# 2656.net
KiCad netlist of a schematic drawn in EAGLE
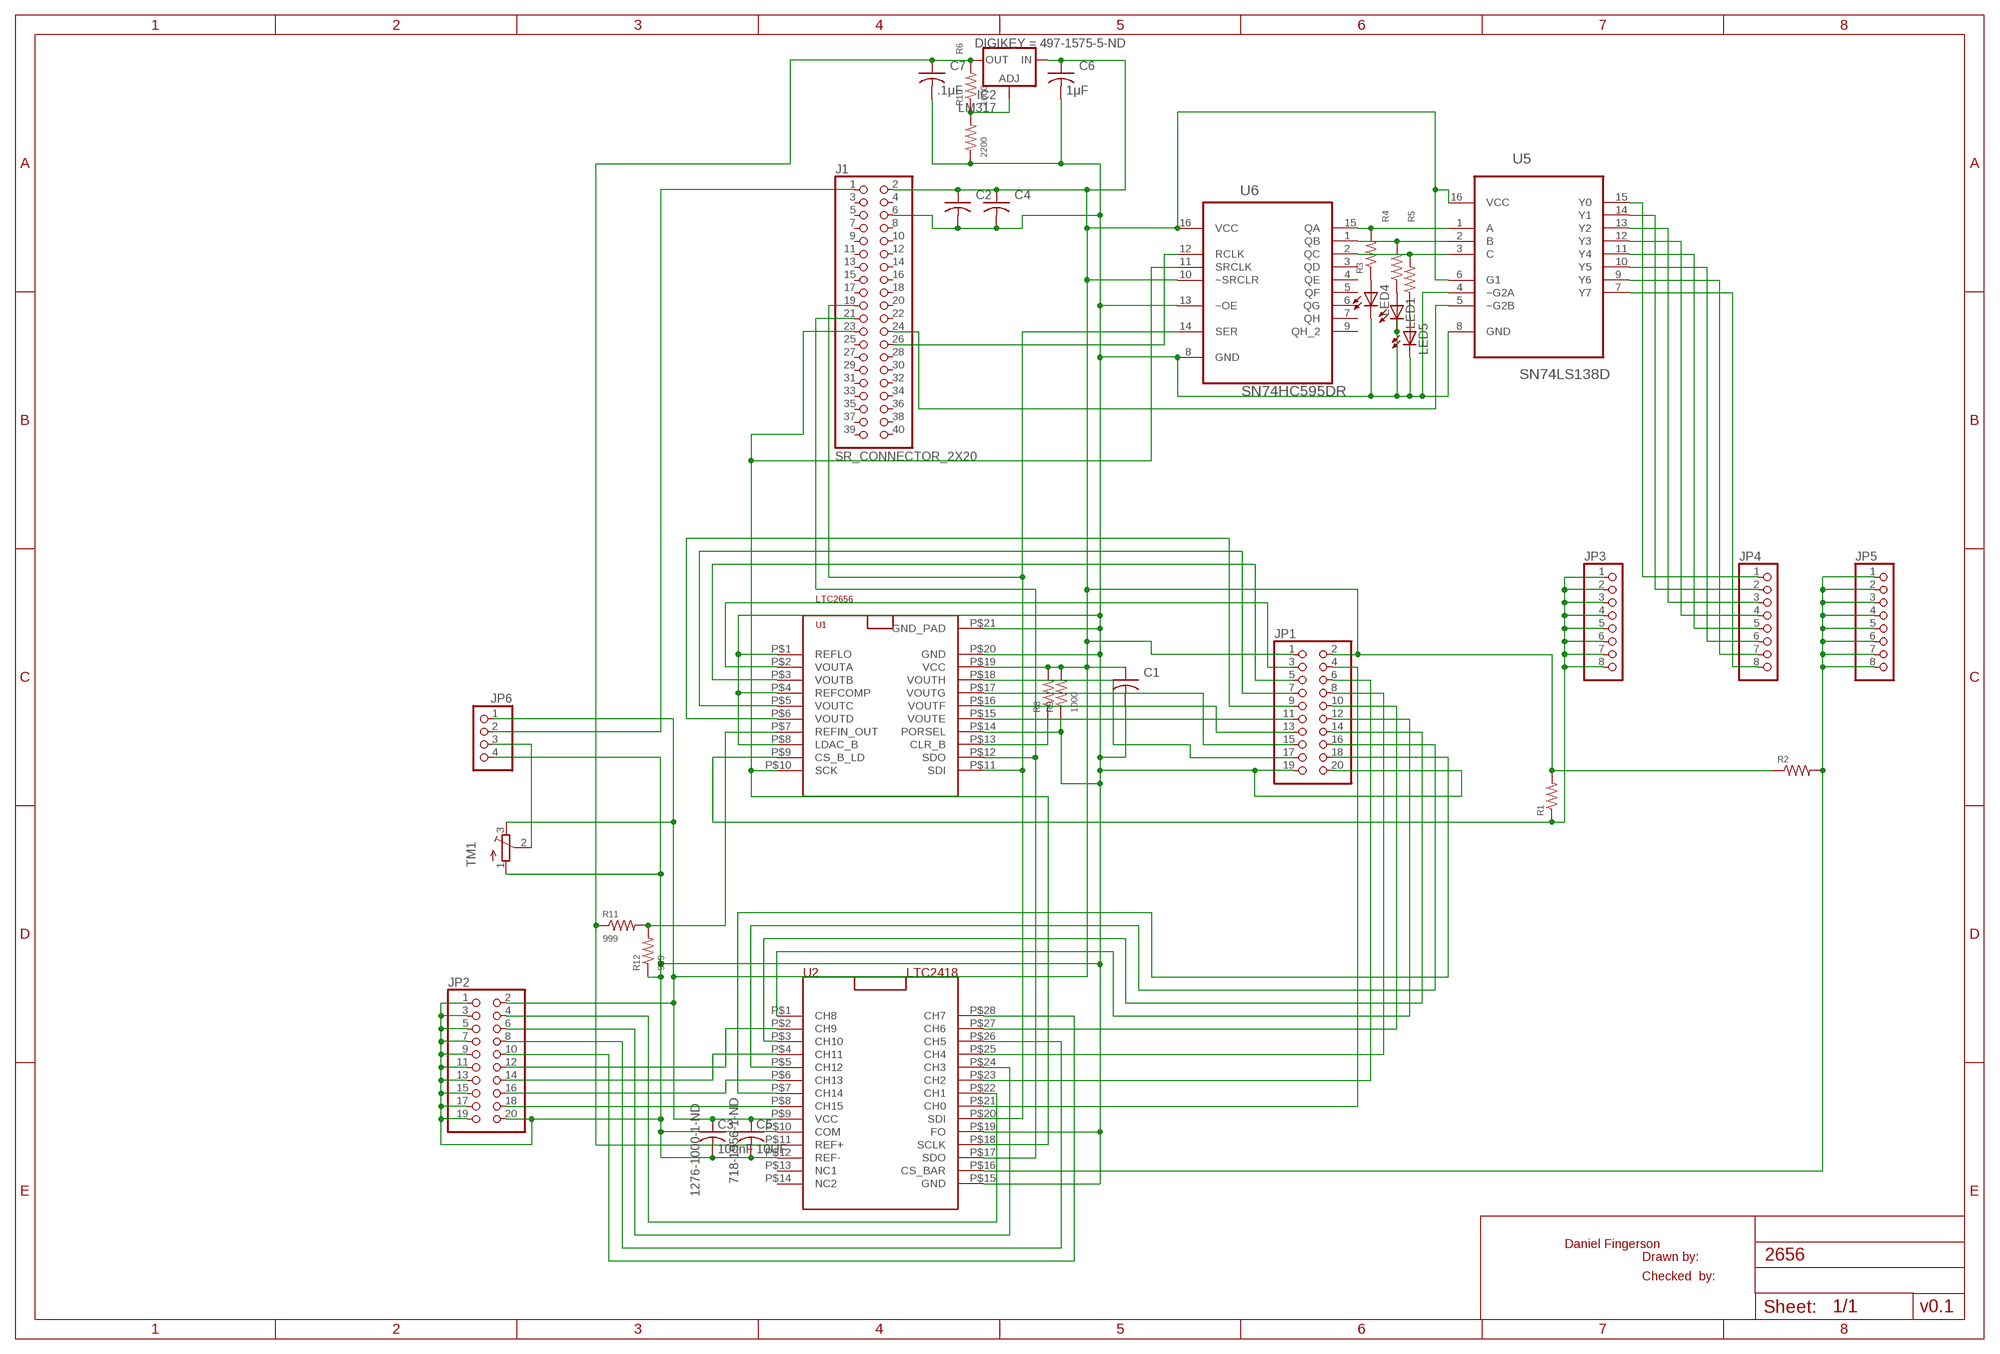
[diagram p0: schematic, sheet 1]

(export (version "E")
  (design (tool "Eeschema 10.0.6"))
  (components
    (comp (ref "C1")
      (value "C-USC1206")
      (footprint "eagle-import:C1206")
      (libsource (lib "eagle-import") (part "C-USC1206"))
    )
    (comp (ref "C2")
      (value "C-USC1206")
      (footprint "eagle-import:C1206")
      (libsource (lib "eagle-import") (part "C-USC1206"))
    )
    (comp (ref "C3")
      (value "100nF")
      (footprint "eagle-import:C1206")
      (fields (field (name "DIGIKEY") "1276-1000-1-ND"))
      (libsource (lib "eagle-import") (part "C-USC1206"))
    )
    (comp (ref "C4")
      (value "C-USC1206")
      (footprint "eagle-import:C1206")
      (libsource (lib "eagle-import") (part "C-USC1206"))
    )
    (comp (ref "C5")
      (value "10UF")
      (footprint "eagle-import:C1206")
      (fields (field (name "DIGIKEY") "718-1956-1-ND"))
      (libsource (lib "eagle-import") (part "C-USC1206"))
    )
    (comp (ref "C6")
      (value "1μF")
      (footprint "eagle-import:C1206")
      (libsource (lib "eagle-import") (part "C-USC1206"))
    )
    (comp (ref "C7")
      (value ".1μF")
      (footprint "eagle-import:C1206")
      (libsource (lib "eagle-import") (part "C-USC1206"))
    )
    (comp (ref "IC2")
      (value "LM317")
      (footprint "eagle-import:317TL")
      (fields (field (name "DIGIKEY") "497-1575-5-ND"))
      (libsource (lib "eagle-import") (part "LM317TL"))
    )
    (comp (ref "J1")
      (value "SR_CONNECTOR_2X20")
      (footprint "eagle-import:SR_CONNECTOR_2X20")
      (libsource (lib "eagle-import") (part "SR_CONNECTOR_2X20"))
    )
    (comp (ref "JP1")
      (value "PINHD-2X10")
      (footprint "eagle-import:2X10")
      (libsource (lib "eagle-import") (part "PINHD-2X10"))
    )
    (comp (ref "JP2")
      (value "PINHD-2X10")
      (footprint "eagle-import:2X10")
      (libsource (lib "eagle-import") (part "PINHD-2X10"))
    )
    (comp (ref "JP3")
      (value "PINHD-1X8BIG")
      (footprint "eagle-import:1X08-BIG")
      (libsource (lib "eagle-import") (part "PINHD-1X8BIG"))
    )
    (comp (ref "JP4")
      (value "PINHD-1X8BIG")
      (footprint "eagle-import:1X08-BIG")
      (libsource (lib "eagle-import") (part "PINHD-1X8BIG"))
    )
    (comp (ref "JP5")
      (value "PINHD-1X8BIG")
      (footprint "eagle-import:1X08-BIG")
      (libsource (lib "eagle-import") (part "PINHD-1X8BIG"))
    )
    (comp (ref "JP6")
      (value "PINHD-1X4")
      (footprint "eagle-import:1X04")
      (libsource (lib "eagle-import") (part "PINHD-1X4"))
    )
    (comp (ref "LED1")
      (value "LEDCHIPLED_1206")
      (footprint "eagle-import:CHIPLED_1206")
      (libsource (lib "eagle-import") (part "LEDCHIPLED_1206"))
    )
    (comp (ref "LED4")
      (value "LEDCHIPLED_1206")
      (footprint "eagle-import:CHIPLED_1206")
      (libsource (lib "eagle-import") (part "LEDCHIPLED_1206"))
    )
    (comp (ref "LED5")
      (value "LEDCHIPLED_1206")
      (footprint "eagle-import:CHIPLED_1206")
      (libsource (lib "eagle-import") (part "LEDCHIPLED_1206"))
    )
    (comp (ref "R1")
      (value "R-US_R1206")
      (footprint "eagle-import:R1206")
      (libsource (lib "eagle-import") (part "R-US_R1206"))
    )
    (comp (ref "R2")
      (value "R-US_R1206")
      (footprint "eagle-import:R1206")
      (libsource (lib "eagle-import") (part "R-US_R1206"))
    )
    (comp (ref "R3")
      (value "R-US_R1206")
      (footprint "eagle-import:R1206")
      (libsource (lib "eagle-import") (part "R-US_R1206"))
    )
    (comp (ref "R4")
      (value "R-US_R1206")
      (footprint "eagle-import:R1206")
      (libsource (lib "eagle-import") (part "R-US_R1206"))
    )
    (comp (ref "R5")
      (value "R-US_R1206")
      (footprint "eagle-import:R1206")
      (libsource (lib "eagle-import") (part "R-US_R1206"))
    )
    (comp (ref "R6")
      (value "1000")
      (footprint "eagle-import:R1206")
      (libsource (lib "eagle-import") (part "R-US_R1206"))
    )
    (comp (ref "R8")
      (value "R-US_R1206")
      (footprint "eagle-import:R1206")
      (libsource (lib "eagle-import") (part "R-US_R1206"))
    )
    (comp (ref "R9")
      (value "1000")
      (footprint "eagle-import:R1206")
      (libsource (lib "eagle-import") (part "R-US_R1206"))
    )
    (comp (ref "R10")
      (value "2200")
      (footprint "eagle-import:R1206")
      (libsource (lib "eagle-import") (part "R-US_R1206"))
    )
    (comp (ref "R11")
      (value "999")
      (footprint "eagle-import:R1206")
      (libsource (lib "eagle-import") (part "R-US_R1206"))
    )
    (comp (ref "R12")
      (value "999")
      (footprint "eagle-import:R1206")
      (libsource (lib "eagle-import") (part "R-US_R1206"))
    )
    (comp (ref "TM1")
      (value "TRIMPOT3386")
      (footprint "eagle-import:TRIM-3386")
      (libsource (lib "eagle-import") (part "TRIMPOT3386"))
    )
    (comp (ref "U1")
      (value "LTC2656")
      (footprint "eagle-import:SR_TSSOP20")
      (libsource (lib "eagle-import") (part "LTC2656"))
    )
    (comp (ref "U2")
      (value "LTC2418")
      (footprint "eagle-import:SR_SSOP28")
      (libsource (lib "eagle-import") (part "LTC2418"))
    )
    (comp (ref "U5")
      (value "SN74LS138D")
      (footprint "eagle-import:SOIC127P600X175-16N")
      (libsource (lib "eagle-import") (part "SN74LS138D"))
    )
    (comp (ref "U6")
      (value "SN74HC595DR")
      (footprint "eagle-import:SOIC127P600X175-16N")
      (fields (field (name "SPICEPREFIX") "X"))
      (libsource (lib "eagle-import") (part "SN74HC595DR"))
    )
  )
  (nets
    (net (code "1") (name "Net-(IC2-ADJ)") (class "Default")
      (node (ref "IC2") (pin "1") (pinfunction "ADJ_1") (pintype "input"))
      (node (ref "R10") (pin "2") (pinfunction "2_2") (pintype "passive"))
      (node (ref "R6") (pin "1") (pinfunction "1_1") (pintype "passive"))
    )
    (net (code "2") (name "Net-(IC2-IN)") (class "Default")
      (node (ref "C1") (pin "1") (pinfunction "1_1") (pintype "passive"))
      (node (ref "C2") (pin "1") (pinfunction "1_1") (pintype "passive"))
      (node (ref "C3") (pin "1") (pinfunction "1_1") (pintype "passive"))
      (node (ref "C4") (pin "1") (pinfunction "1_1") (pintype "passive"))
      (node (ref "C5") (pin "1") (pinfunction "1_1") (pintype "passive"))
      (node (ref "C6") (pin "1") (pinfunction "1_1") (pintype "passive"))
      (node (ref "IC2") (pin "3") (pinfunction "IN_3") (pintype "input"))
      (node (ref "J1") (pin "2") (pinfunction "2_2") (pintype "passive"))
      (node (ref "JP1") (pin "1") (pinfunction "1_1") (pintype "passive"))
      (node (ref "JP1") (pin "2") (pinfunction "2_2") (pintype "passive"))
      (node (ref "JP2") (pin "2") (pinfunction "2_2") (pintype "passive"))
      (node (ref "JP6") (pin "1") (pinfunction "1_1") (pintype "passive"))
      (node (ref "R1") (pin "2") (pinfunction "2_2") (pintype "passive"))
      (node (ref "R2") (pin "1") (pinfunction "1_1") (pintype "passive"))
      (node (ref "R8") (pin "2") (pinfunction "2_2") (pintype "passive"))
      (node (ref "R9") (pin "2") (pinfunction "2_2") (pintype "passive"))
      (node (ref "TM1") (pin "3") (pinfunction "E_3") (pintype "passive"))
      (node (ref "U1") (pin "P$19") (pinfunction "VCC_P$19") (pintype "bidirectional"))
      (node (ref "U2") (pin "P$9") (pinfunction "VCC_P$9") (pintype "bidirectional"))
      (node (ref "U5") (pin "16") (pinfunction "VCC_16") (pintype "power_in"))
      (node (ref "U5") (pin "6") (pinfunction "G1_6") (pintype "input"))
      (node (ref "U6") (pin "10") (pinfunction "~{SRCLR}_10") (pintype "input"))
      (node (ref "U6") (pin "16") (pinfunction "VCC_16") (pintype "power_in"))
    )
    (net (code "3") (name "Net-(IC2-OUT)") (class "Default")
      (node (ref "C7") (pin "1") (pinfunction "1_1") (pintype "passive"))
      (node (ref "IC2") (pin "2") (pinfunction "OUT_2") (pintype "passive"))
      (node (ref "R11") (pin "1") (pinfunction "1_1") (pintype "passive"))
      (node (ref "R6") (pin "2") (pinfunction "2_2") (pintype "passive"))
      (node (ref "U2") (pin "P$11") (pinfunction "REF+_P$11") (pintype "bidirectional"))
    )
    (net (code "4") (name "Net-(J1-Pad1)") (class "Default")
      (node (ref "J1") (pin "1") (pinfunction "1_1") (pintype "passive"))
      (node (ref "JP6") (pin "2") (pinfunction "2_2") (pintype "passive"))
    )
    (net (code "5") (name "Net-(LED1-PadA)") (class "Default")
      (node (ref "LED1") (pin "A") (pinfunction "A_A") (pintype "passive"))
      (node (ref "R4") (pin "1") (pinfunction "1_1") (pintype "passive"))
    )
    (net (code "6") (name "Net-(LED4-PadA)") (class "Default")
      (node (ref "LED4") (pin "A") (pinfunction "A_A") (pintype "passive"))
      (node (ref "R3") (pin "1") (pinfunction "1_1") (pintype "passive"))
    )
    (net (code "7") (name "Net-(LED5-PadA)") (class "Default")
      (node (ref "LED5") (pin "A") (pinfunction "A_A") (pintype "passive"))
      (node (ref "R5") (pin "1") (pinfunction "1_1") (pintype "passive"))
    )
    (net (code "8") (name "Net-(TM1-A)") (class "Default")
      (node (ref "C1") (pin "2") (pinfunction "2_2") (pintype "passive"))
      (node (ref "C2") (pin "2") (pinfunction "2_2") (pintype "passive"))
      (node (ref "C3") (pin "2") (pinfunction "2_2") (pintype "passive"))
      (node (ref "C4") (pin "2") (pinfunction "2_2") (pintype "passive"))
      (node (ref "C5") (pin "2") (pinfunction "2_2") (pintype "passive"))
      (node (ref "C6") (pin "2") (pinfunction "2_2") (pintype "passive"))
      (node (ref "C7") (pin "2") (pinfunction "2_2") (pintype "passive"))
      (node (ref "J1") (pin "6") (pinfunction "6_6") (pintype "passive"))
      (node (ref "JP1") (pin "19") (pinfunction "19_19") (pintype "passive"))
      (node (ref "JP1") (pin "20") (pinfunction "20_20") (pintype "passive"))
      (node (ref "JP2") (pin "1") (pinfunction "1_1") (pintype "passive"))
      (node (ref "JP2") (pin "11") (pinfunction "11_11") (pintype "passive"))
      (node (ref "JP2") (pin "13") (pinfunction "13_13") (pintype "passive"))
      (node (ref "JP2") (pin "15") (pinfunction "15_15") (pintype "passive"))
      (node (ref "JP2") (pin "17") (pinfunction "17_17") (pintype "passive"))
      (node (ref "JP2") (pin "19") (pinfunction "19_19") (pintype "passive"))
      (node (ref "JP2") (pin "20") (pinfunction "20_20") (pintype "passive"))
      (node (ref "JP2") (pin "3") (pinfunction "3_3") (pintype "passive"))
      (node (ref "JP2") (pin "5") (pinfunction "5_5") (pintype "passive"))
      (node (ref "JP2") (pin "7") (pinfunction "7_7") (pintype "passive"))
      (node (ref "JP2") (pin "9") (pinfunction "9_9") (pintype "passive"))
      (node (ref "JP6") (pin "4") (pinfunction "4_4") (pintype "passive"))
      (node (ref "LED1") (pin "C") (pinfunction "C_C") (pintype "passive"))
      (node (ref "LED4") (pin "C") (pinfunction "C_C") (pintype "passive"))
      (node (ref "LED5") (pin "C") (pinfunction "C_C") (pintype "passive"))
      (node (ref "R10") (pin "1") (pinfunction "1_1") (pintype "passive"))
      (node (ref "R12") (pin "1") (pinfunction "1_1") (pintype "passive"))
      (node (ref "R9") (pin "1") (pinfunction "1_1") (pintype "passive"))
      (node (ref "TM1") (pin "1") (pinfunction "A_1") (pintype "passive"))
      (node (ref "U1") (pin "P$1") (pinfunction "REFLO_P$1") (pintype "bidirectional"))
      (node (ref "U1") (pin "P$14") (pinfunction "PORSEL_P$14") (pintype "bidirectional"))
      (node (ref "U1") (pin "P$20") (pinfunction "GND_P$20") (pintype "bidirectional"))
      (node (ref "U1") (pin "P$21") (pinfunction "GND_PAD_P$21") (pintype "bidirectional"))
      (node (ref "U1") (pin "P$4") (pinfunction "REFCOMP_P$4") (pintype "bidirectional"))
      (node (ref "U1") (pin "P$8") (pinfunction "LDAC_B_P$8") (pintype "bidirectional"))
      (node (ref "U2") (pin "P$10") (pinfunction "COM_P$10") (pintype "bidirectional"))
      (node (ref "U2") (pin "P$12") (pinfunction "REF-_P$12") (pintype "bidirectional"))
      (node (ref "U2") (pin "P$15") (pinfunction "GND_P$15") (pintype "bidirectional"))
      (node (ref "U2") (pin "P$19") (pinfunction "FO_P$19") (pintype "bidirectional"))
      (node (ref "U5") (pin "4") (pinfunction "~{G2A}_4") (pintype "input"))
      (node (ref "U5") (pin "8") (pinfunction "GND_8") (pintype "passive"))
      (node (ref "U6") (pin "13") (pinfunction "~{OE}_13") (pintype "input"))
      (node (ref "U6") (pin "8") (pinfunction "GND_8") (pintype "passive"))
    )
    (net (code "9") (name "Net-(TM1-S)") (class "Default")
      (node (ref "JP6") (pin "3") (pinfunction "3_3") (pintype "passive"))
      (node (ref "TM1") (pin "2") (pinfunction "S_2") (pintype "passive"))
    )
    (net (code "10") (name "Net-(U1-CLR_B)") (class "Default")
      (node (ref "R8") (pin "1") (pinfunction "1_1") (pintype "passive"))
      (node (ref "U1") (pin "P$13") (pinfunction "CLR_B_P$13") (pintype "bidirectional"))
    )
    (net (code "11") (name "Net-(U1-CS_B_LD)") (class "Default")
      (node (ref "JP3") (pin "1") (pinfunction "1_1") (pintype "passive"))
      (node (ref "JP3") (pin "2") (pinfunction "2_2") (pintype "passive"))
      (node (ref "JP3") (pin "3") (pinfunction "3_3") (pintype "passive"))
      (node (ref "JP3") (pin "4") (pinfunction "4_4") (pintype "passive"))
      (node (ref "JP3") (pin "5") (pinfunction "5_5") (pintype "passive"))
      (node (ref "JP3") (pin "6") (pinfunction "6_6") (pintype "passive"))
      (node (ref "JP3") (pin "7") (pinfunction "7_7") (pintype "passive"))
      (node (ref "JP3") (pin "8") (pinfunction "8_8") (pintype "passive"))
      (node (ref "R1") (pin "1") (pinfunction "1_1") (pintype "passive"))
      (node (ref "U1") (pin "P$9") (pinfunction "CS_B_LD_P$9") (pintype "bidirectional"))
    )
    (net (code "12") (name "Net-(U1-REFIN_OUT)") (class "Default")
      (node (ref "R11") (pin "2") (pinfunction "2_2") (pintype "passive"))
      (node (ref "R12") (pin "2") (pinfunction "2_2") (pintype "passive"))
      (node (ref "U1") (pin "P$7") (pinfunction "REFIN_OUT_P$7") (pintype "bidirectional"))
    )
    (net (code "13") (name "Net-(U1-SCK)") (class "Default")
      (node (ref "J1") (pin "23") (pinfunction "23_23") (pintype "passive"))
      (node (ref "U1") (pin "P$10") (pinfunction "SCK_P$10") (pintype "bidirectional"))
      (node (ref "U2") (pin "P$18") (pinfunction "SCLK_P$18") (pintype "bidirectional"))
      (node (ref "U6") (pin "11") (pinfunction "SRCLK_11") (pintype "input"))
    )
    (net (code "14") (name "Net-(U1-SDI)") (class "Default")
      (node (ref "J1") (pin "19") (pinfunction "19_19") (pintype "passive"))
      (node (ref "U1") (pin "P$11") (pinfunction "SDI_P$11") (pintype "bidirectional"))
      (node (ref "U2") (pin "P$20") (pinfunction "SDI_P$20") (pintype "bidirectional"))
      (node (ref "U6") (pin "14") (pinfunction "SER_14") (pintype "input"))
    )
    (net (code "15") (name "Net-(U1-SDO)") (class "Default")
      (node (ref "J1") (pin "21") (pinfunction "21_21") (pintype "passive"))
      (node (ref "U1") (pin "P$12") (pinfunction "SDO_P$12") (pintype "bidirectional"))
      (node (ref "U2") (pin "P$17") (pinfunction "SDO_P$17") (pintype "bidirectional"))
    )
    (net (code "16") (name "Net-(U1-VOUTA)") (class "Default")
      (node (ref "JP1") (pin "3") (pinfunction "3_3") (pintype "passive"))
      (node (ref "U1") (pin "P$2") (pinfunction "VOUTA_P$2") (pintype "bidirectional"))
    )
    (net (code "17") (name "Net-(U1-VOUTB)") (class "Default")
      (node (ref "JP1") (pin "5") (pinfunction "5_5") (pintype "passive"))
      (node (ref "U1") (pin "P$3") (pinfunction "VOUTB_P$3") (pintype "bidirectional"))
    )
    (net (code "18") (name "Net-(U1-VOUTC)") (class "Default")
      (node (ref "JP1") (pin "7") (pinfunction "7_7") (pintype "passive"))
      (node (ref "U1") (pin "P$5") (pinfunction "VOUTC_P$5") (pintype "bidirectional"))
    )
    (net (code "19") (name "Net-(U1-VOUTD)") (class "Default")
      (node (ref "JP1") (pin "9") (pinfunction "9_9") (pintype "passive"))
      (node (ref "U1") (pin "P$6") (pinfunction "VOUTD_P$6") (pintype "bidirectional"))
    )
    (net (code "20") (name "Net-(U1-VOUTE)") (class "Default")
      (node (ref "JP1") (pin "11") (pinfunction "11_11") (pintype "passive"))
      (node (ref "U1") (pin "P$15") (pinfunction "VOUTE_P$15") (pintype "bidirectional"))
    )
    (net (code "21") (name "Net-(U1-VOUTF)") (class "Default")
      (node (ref "JP1") (pin "13") (pinfunction "13_13") (pintype "passive"))
      (node (ref "U1") (pin "P$16") (pinfunction "VOUTF_P$16") (pintype "bidirectional"))
    )
    (net (code "22") (name "Net-(U1-VOUTG)") (class "Default")
      (node (ref "JP1") (pin "15") (pinfunction "15_15") (pintype "passive"))
      (node (ref "U1") (pin "P$17") (pinfunction "VOUTG_P$17") (pintype "bidirectional"))
    )
    (net (code "23") (name "Net-(U1-VOUTH)") (class "Default")
      (node (ref "JP1") (pin "17") (pinfunction "17_17") (pintype "passive"))
      (node (ref "U1") (pin "P$18") (pinfunction "VOUTH_P$18") (pintype "bidirectional"))
    )
    (net (code "24") (name "Net-(U2-CH0)") (class "Default")
      (node (ref "JP1") (pin "4") (pinfunction "4_4") (pintype "passive"))
      (node (ref "U2") (pin "P$21") (pinfunction "CH0_P$21") (pintype "bidirectional"))
    )
    (net (code "25") (name "Net-(U2-CH1)") (class "Default")
      (node (ref "JP2") (pin "4") (pinfunction "4_4") (pintype "passive"))
      (node (ref "U2") (pin "P$22") (pinfunction "CH1_P$22") (pintype "bidirectional"))
    )
    (net (code "26") (name "Net-(U2-CH2)") (class "Default")
      (node (ref "JP1") (pin "6") (pinfunction "6_6") (pintype "passive"))
      (node (ref "U2") (pin "P$23") (pinfunction "CH2_P$23") (pintype "bidirectional"))
    )
    (net (code "27") (name "Net-(U2-CH3)") (class "Default")
      (node (ref "JP2") (pin "6") (pinfunction "6_6") (pintype "passive"))
      (node (ref "U2") (pin "P$24") (pinfunction "CH3_P$24") (pintype "bidirectional"))
    )
    (net (code "28") (name "Net-(U2-CH4)") (class "Default")
      (node (ref "JP1") (pin "8") (pinfunction "8_8") (pintype "passive"))
      (node (ref "U2") (pin "P$25") (pinfunction "CH4_P$25") (pintype "bidirectional"))
    )
    (net (code "29") (name "Net-(U2-CH5)") (class "Default")
      (node (ref "JP2") (pin "8") (pinfunction "8_8") (pintype "passive"))
      (node (ref "U2") (pin "P$26") (pinfunction "CH5_P$26") (pintype "bidirectional"))
    )
    (net (code "30") (name "Net-(U2-CH6)") (class "Default")
      (node (ref "JP1") (pin "10") (pinfunction "10_10") (pintype "passive"))
      (node (ref "U2") (pin "P$27") (pinfunction "CH6_P$27") (pintype "bidirectional"))
    )
    (net (code "31") (name "Net-(U2-CH7)") (class "Default")
      (node (ref "JP2") (pin "10") (pinfunction "10_10") (pintype "passive"))
      (node (ref "U2") (pin "P$28") (pinfunction "CH7_P$28") (pintype "bidirectional"))
    )
    (net (code "32") (name "Net-(U2-CH8)") (class "Default")
      (node (ref "JP1") (pin "12") (pinfunction "12_12") (pintype "passive"))
      (node (ref "U2") (pin "P$1") (pinfunction "CH8_P$1") (pintype "bidirectional"))
    )
    (net (code "33") (name "Net-(U2-CH9)") (class "Default")
      (node (ref "JP2") (pin "12") (pinfunction "12_12") (pintype "passive"))
      (node (ref "U2") (pin "P$2") (pinfunction "CH9_P$2") (pintype "bidirectional"))
    )
    (net (code "34") (name "Net-(U2-CH10)") (class "Default")
      (node (ref "JP1") (pin "14") (pinfunction "14_14") (pintype "passive"))
      (node (ref "U2") (pin "P$3") (pinfunction "CH10_P$3") (pintype "bidirectional"))
    )
    (net (code "35") (name "Net-(U2-CH11)") (class "Default")
      (node (ref "JP2") (pin "14") (pinfunction "14_14") (pintype "passive"))
      (node (ref "U2") (pin "P$4") (pinfunction "CH11_P$4") (pintype "bidirectional"))
    )
    (net (code "36") (name "Net-(U2-CH12)") (class "Default")
      (node (ref "JP1") (pin "16") (pinfunction "16_16") (pintype "passive"))
      (node (ref "U2") (pin "P$5") (pinfunction "CH12_P$5") (pintype "bidirectional"))
    )
    (net (code "37") (name "Net-(U2-CH13)") (class "Default")
      (node (ref "JP2") (pin "16") (pinfunction "16_16") (pintype "passive"))
      (node (ref "U2") (pin "P$6") (pinfunction "CH13_P$6") (pintype "bidirectional"))
    )
    (net (code "38") (name "Net-(U2-CH14)") (class "Default")
      (node (ref "JP1") (pin "18") (pinfunction "18_18") (pintype "passive"))
      (node (ref "U2") (pin "P$7") (pinfunction "CH14_P$7") (pintype "bidirectional"))
    )
    (net (code "39") (name "Net-(U2-CH15)") (class "Default")
      (node (ref "JP2") (pin "18") (pinfunction "18_18") (pintype "passive"))
      (node (ref "U2") (pin "P$8") (pinfunction "CH15_P$8") (pintype "bidirectional"))
    )
    (net (code "40") (name "Net-(U2-CS_BAR)") (class "Default")
      (node (ref "JP5") (pin "1") (pinfunction "1_1") (pintype "passive"))
      (node (ref "JP5") (pin "2") (pinfunction "2_2") (pintype "passive"))
      (node (ref "JP5") (pin "3") (pinfunction "3_3") (pintype "passive"))
      (node (ref "JP5") (pin "4") (pinfunction "4_4") (pintype "passive"))
      (node (ref "JP5") (pin "5") (pinfunction "5_5") (pintype "passive"))
      (node (ref "JP5") (pin "6") (pinfunction "6_6") (pintype "passive"))
      (node (ref "JP5") (pin "7") (pinfunction "7_7") (pintype "passive"))
      (node (ref "JP5") (pin "8") (pinfunction "8_8") (pintype "passive"))
      (node (ref "R2") (pin "2") (pinfunction "2_2") (pintype "passive"))
      (node (ref "U2") (pin "P$16") (pinfunction "CS_BAR_P$16") (pintype "bidirectional"))
    )
    (net (code "41") (name "Net-(U5-A)") (class "Default")
      (node (ref "R3") (pin "2") (pinfunction "2_2") (pintype "passive"))
      (node (ref "U5") (pin "1") (pinfunction "A_1") (pintype "input"))
      (node (ref "U6") (pin "15") (pinfunction "QA_15") (pintype "output"))
    )
    (net (code "42") (name "Net-(U5-B)") (class "Default")
      (node (ref "R4") (pin "2") (pinfunction "2_2") (pintype "passive"))
      (node (ref "U5") (pin "2") (pinfunction "B_2") (pintype "input"))
      (node (ref "U6") (pin "1") (pinfunction "QB_1") (pintype "output"))
    )
    (net (code "43") (name "Net-(U5-C)") (class "Default")
      (node (ref "R5") (pin "2") (pinfunction "2_2") (pintype "passive"))
      (node (ref "U5") (pin "3") (pinfunction "C_3") (pintype "input"))
      (node (ref "U6") (pin "2") (pinfunction "QC_2") (pintype "output"))
    )
    (net (code "44") (name "Net-(U5-Y0)") (class "Default")
      (node (ref "JP4") (pin "1") (pinfunction "1_1") (pintype "passive"))
      (node (ref "U5") (pin "15") (pinfunction "Y0_15") (pintype "output"))
    )
    (net (code "45") (name "Net-(U5-Y1)") (class "Default")
      (node (ref "JP4") (pin "2") (pinfunction "2_2") (pintype "passive"))
      (node (ref "U5") (pin "14") (pinfunction "Y1_14") (pintype "output"))
    )
    (net (code "46") (name "Net-(U5-Y2)") (class "Default")
      (node (ref "JP4") (pin "3") (pinfunction "3_3") (pintype "passive"))
      (node (ref "U5") (pin "13") (pinfunction "Y2_13") (pintype "output"))
    )
    (net (code "47") (name "Net-(U5-Y3)") (class "Default")
      (node (ref "JP4") (pin "4") (pinfunction "4_4") (pintype "passive"))
      (node (ref "U5") (pin "12") (pinfunction "Y3_12") (pintype "output"))
    )
    (net (code "48") (name "Net-(U5-Y4)") (class "Default")
      (node (ref "JP4") (pin "5") (pinfunction "5_5") (pintype "passive"))
      (node (ref "U5") (pin "11") (pinfunction "Y4_11") (pintype "output"))
    )
    (net (code "49") (name "Net-(U5-Y5)") (class "Default")
      (node (ref "JP4") (pin "6") (pinfunction "6_6") (pintype "passive"))
      (node (ref "U5") (pin "10") (pinfunction "Y5_10") (pintype "output"))
    )
    (net (code "50") (name "Net-(U5-Y6)") (class "Default")
      (node (ref "JP4") (pin "7") (pinfunction "7_7") (pintype "passive"))
      (node (ref "U5") (pin "9") (pinfunction "Y6_9") (pintype "output"))
    )
    (net (code "51") (name "Net-(U5-Y7)") (class "Default")
      (node (ref "JP4") (pin "8") (pinfunction "8_8") (pintype "passive"))
      (node (ref "U5") (pin "7") (pinfunction "Y7_7") (pintype "output"))
    )
    (net (code "52") (name "Net-(U5-~{G2B})") (class "Default")
      (node (ref "J1") (pin "24") (pinfunction "24_24") (pintype "passive"))
      (node (ref "U5") (pin "5") (pinfunction "~{G2B}_5") (pintype "input"))
    )
    (net (code "53") (name "Net-(U6-RCLK)") (class "Default")
      (node (ref "J1") (pin "26") (pinfunction "26_26") (pintype "passive"))
      (node (ref "U6") (pin "12") (pinfunction "RCLK_12") (pintype "input"))
    )
    (net (code "54") (name "unconnected-(J1-Pad3)") (class "Default")
      (node (ref "J1") (pin "3") (pinfunction "3_3") (pintype "passive"))
    )
    (net (code "55") (name "unconnected-(J1-Pad4)") (class "Default")
      (node (ref "J1") (pin "4") (pinfunction "4_4") (pintype "passive"))
    )
    (net (code "56") (name "unconnected-(J1-Pad5)") (class "Default")
      (node (ref "J1") (pin "5") (pinfunction "5_5") (pintype "passive"))
    )
    (net (code "57") (name "unconnected-(J1-Pad7)") (class "Default")
      (node (ref "J1") (pin "7") (pinfunction "7_7") (pintype "passive"))
    )
    (net (code "58") (name "unconnected-(J1-Pad8)") (class "Default")
      (node (ref "J1") (pin "8") (pinfunction "8_8") (pintype "passive"))
    )
    (net (code "59") (name "unconnected-(J1-Pad9)") (class "Default")
      (node (ref "J1") (pin "9") (pinfunction "9_9") (pintype "passive"))
    )
    (net (code "60") (name "unconnected-(J1-Pad10)") (class "Default")
      (node (ref "J1") (pin "10") (pinfunction "10_10") (pintype "passive"))
    )
    (net (code "61") (name "unconnected-(J1-Pad11)") (class "Default")
      (node (ref "J1") (pin "11") (pinfunction "11_11") (pintype "passive"))
    )
    (net (code "62") (name "unconnected-(J1-Pad12)") (class "Default")
      (node (ref "J1") (pin "12") (pinfunction "12_12") (pintype "passive"))
    )
    (net (code "63") (name "unconnected-(J1-Pad13)") (class "Default")
      (node (ref "J1") (pin "13") (pinfunction "13_13") (pintype "passive"))
    )
    (net (code "64") (name "unconnected-(J1-Pad14)") (class "Default")
      (node (ref "J1") (pin "14") (pinfunction "14_14") (pintype "passive"))
    )
    (net (code "65") (name "unconnected-(J1-Pad15)") (class "Default")
      (node (ref "J1") (pin "15") (pinfunction "15_15") (pintype "passive"))
    )
    (net (code "66") (name "unconnected-(J1-Pad16)") (class "Default")
      (node (ref "J1") (pin "16") (pinfunction "16_16") (pintype "passive"))
    )
    (net (code "67") (name "unconnected-(J1-Pad17)") (class "Default")
      (node (ref "J1") (pin "17") (pinfunction "17_17") (pintype "passive"))
    )
    (net (code "68") (name "unconnected-(J1-Pad18)") (class "Default")
      (node (ref "J1") (pin "18") (pinfunction "18_18") (pintype "passive"))
    )
    (net (code "69") (name "unconnected-(J1-Pad20)") (class "Default")
      (node (ref "J1") (pin "20") (pinfunction "20_20") (pintype "passive"))
    )
    (net (code "70") (name "unconnected-(J1-Pad22)") (class "Default")
      (node (ref "J1") (pin "22") (pinfunction "22_22") (pintype "passive"))
    )
    (net (code "71") (name "unconnected-(J1-Pad25)") (class "Default")
      (node (ref "J1") (pin "25") (pinfunction "25_25") (pintype "passive"))
    )
    (net (code "72") (name "unconnected-(J1-Pad27)") (class "Default")
      (node (ref "J1") (pin "27") (pinfunction "27_27") (pintype "passive"))
    )
    (net (code "73") (name "unconnected-(J1-Pad28)") (class "Default")
      (node (ref "J1") (pin "28") (pinfunction "28_28") (pintype "passive"))
    )
    (net (code "74") (name "unconnected-(J1-Pad29)") (class "Default")
      (node (ref "J1") (pin "29") (pinfunction "29_29") (pintype "passive"))
    )
    (net (code "75") (name "unconnected-(J1-Pad30)") (class "Default")
      (node (ref "J1") (pin "30") (pinfunction "30_30") (pintype "passive"))
    )
    (net (code "76") (name "unconnected-(J1-Pad31)") (class "Default")
      (node (ref "J1") (pin "31") (pinfunction "31_31") (pintype "passive"))
    )
    (net (code "77") (name "unconnected-(J1-Pad32)") (class "Default")
      (node (ref "J1") (pin "32") (pinfunction "32_32") (pintype "passive"))
    )
    (net (code "78") (name "unconnected-(J1-Pad33)") (class "Default")
      (node (ref "J1") (pin "33") (pinfunction "33_33") (pintype "passive"))
    )
    (net (code "79") (name "unconnected-(J1-Pad34)") (class "Default")
      (node (ref "J1") (pin "34") (pinfunction "34_34") (pintype "passive"))
    )
    (net (code "80") (name "unconnected-(J1-Pad35)") (class "Default")
      (node (ref "J1") (pin "35") (pinfunction "35_35") (pintype "passive"))
    )
    (net (code "81") (name "unconnected-(J1-Pad36)") (class "Default")
      (node (ref "J1") (pin "36") (pinfunction "36_36") (pintype "passive"))
    )
    (net (code "82") (name "unconnected-(J1-Pad37)") (class "Default")
      (node (ref "J1") (pin "37") (pinfunction "37_37") (pintype "passive"))
    )
    (net (code "83") (name "unconnected-(J1-Pad38)") (class "Default")
      (node (ref "J1") (pin "38") (pinfunction "38_38") (pintype "passive"))
    )
    (net (code "84") (name "unconnected-(J1-Pad39)") (class "Default")
      (node (ref "J1") (pin "39") (pinfunction "39_39") (pintype "passive"))
    )
    (net (code "85") (name "unconnected-(J1-Pad40)") (class "Default")
      (node (ref "J1") (pin "40") (pinfunction "40_40") (pintype "passive"))
    )
    (net (code "86") (name "unconnected-(U2-NC1-PadP$13)") (class "Default")
      (node (ref "U2") (pin "P$13") (pinfunction "NC1_P$13") (pintype "bidirectional"))
    )
    (net (code "87") (name "unconnected-(U2-NC2-PadP$14)") (class "Default")
      (node (ref "U2") (pin "P$14") (pinfunction "NC2_P$14") (pintype "bidirectional"))
    )
    (net (code "88") (name "unconnected-(U6-QD-Pad3)") (class "Default")
      (node (ref "U6") (pin "3") (pinfunction "QD_3") (pintype "output"))
    )
    (net (code "89") (name "unconnected-(U6-QE-Pad4)") (class "Default")
      (node (ref "U6") (pin "4") (pinfunction "QE_4") (pintype "output"))
    )
    (net (code "90") (name "unconnected-(U6-QF-Pad5)") (class "Default")
      (node (ref "U6") (pin "5") (pinfunction "QF_5") (pintype "output"))
    )
    (net (code "91") (name "unconnected-(U6-QG-Pad6)") (class "Default")
      (node (ref "U6") (pin "6") (pinfunction "QG_6") (pintype "output"))
    )
    (net (code "92") (name "unconnected-(U6-QH-Pad7)") (class "Default")
      (node (ref "U6") (pin "7") (pinfunction "QH_7") (pintype "output"))
    )
    (net (code "93") (name "unconnected-(U6-QH_2-Pad9)") (class "Default")
      (node (ref "U6") (pin "9") (pinfunction "QH_2_9") (pintype "output"))
    )
  )
)
